# untitled.net
KiCad netlist of a schematic drawn in EAGLE
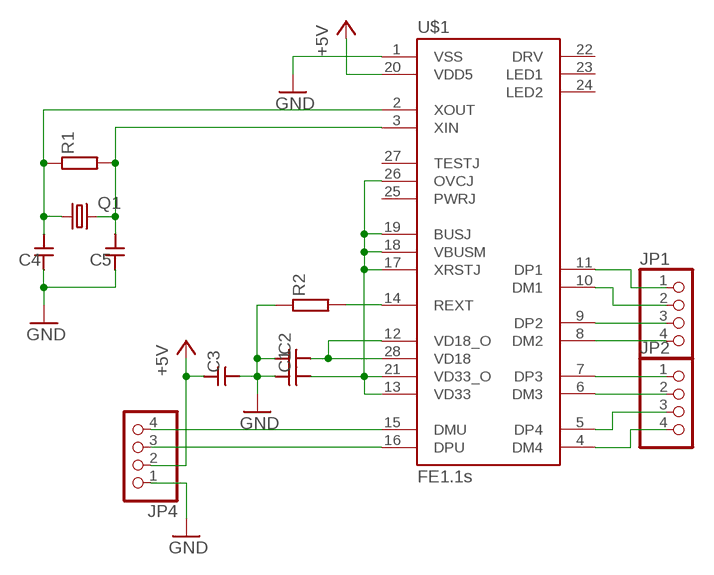
[diagram p0: schematic, sheet 1]

(export (version "E")
  (design (tool "Eeschema 10.0.6"))
  (components
    (comp (ref "C1")
      (value "CAPACITOR1608")
      (footprint "eagle-import:SMD1608")
      (libsource (lib "eagle-import") (part "CAPACITOR1608"))
    )
    (comp (ref "C2")
      (value "CAPACITOR1608")
      (footprint "eagle-import:SMD1608")
      (libsource (lib "eagle-import") (part "CAPACITOR1608"))
    )
    (comp (ref "C3")
      (value "CAPACITOR1608")
      (footprint "eagle-import:SMD1608")
      (libsource (lib "eagle-import") (part "CAPACITOR1608"))
    )
    (comp (ref "C4")
      (value "CAPACITOR1608")
      (footprint "eagle-import:SMD1608")
      (libsource (lib "eagle-import") (part "CAPACITOR1608"))
    )
    (comp (ref "C5")
      (value "CAPACITOR1608")
      (footprint "eagle-import:SMD1608")
      (libsource (lib "eagle-import") (part "CAPACITOR1608"))
    )
    (comp (ref "JP1")
      (value "PINHD-1X4")
      (footprint "eagle-import:1X04")
      (libsource (lib "eagle-import") (part "PINHD-1X4"))
    )
    (comp (ref "JP2")
      (value "PINHD-1X4")
      (footprint "eagle-import:1X04")
      (libsource (lib "eagle-import") (part "PINHD-1X4"))
    )
    (comp (ref "JP4")
      (value "PINHD-1X4")
      (footprint "eagle-import:1X04")
      (libsource (lib "eagle-import") (part "PINHD-1X4"))
    )
    (comp (ref "Q1")
      (value "CRYSTALHC49S")
      (footprint "eagle-import:HC49_S")
      (libsource (lib "eagle-import") (part "CRYSTALHC49S"))
    )
    (comp (ref "R1")
      (value "RESISTOR1608")
      (footprint "eagle-import:SMD1608")
      (libsource (lib "eagle-import") (part "RESISTOR1608"))
    )
    (comp (ref "R2")
      (value "RESISTOR1608")
      (footprint "eagle-import:SMD1608")
      (libsource (lib "eagle-import") (part "RESISTOR1608"))
    )
    (comp (ref "U$1")
      (value "FE1.1S")
      (footprint "eagle-import:FE1.1S_SSOP-28")
      (libsource (lib "eagle-import") (part "FE1.1S"))
    )
  )
  (nets
    (net (code "1") (name "+5V") (class "Default")
      (node (ref "C3") (pin "1") (pinfunction "1_1") (pintype "passive"))
      (node (ref "JP4") (pin "2") (pinfunction "2_2") (pintype "passive"))
      (node (ref "U$1") (pin "20") (pinfunction "VDD5_20") (pintype "bidirectional"))
    )
    (net (code "2") (name "GND") (class "Default")
      (node (ref "C1") (pin "1") (pinfunction "1_1") (pintype "passive"))
      (node (ref "C2") (pin "1") (pinfunction "1_1") (pintype "passive"))
      (node (ref "C3") (pin "2") (pinfunction "2_2") (pintype "passive"))
      (node (ref "C4") (pin "1") (pinfunction "1_1") (pintype "passive"))
      (node (ref "C5") (pin "1") (pinfunction "1_1") (pintype "passive"))
      (node (ref "JP4") (pin "1") (pinfunction "1_1") (pintype "passive"))
      (node (ref "R2") (pin "1") (pinfunction "1_1") (pintype "passive"))
      (node (ref "U$1") (pin "1") (pinfunction "VSS_1") (pintype "bidirectional"))
    )
    (net (code "3") (name "Net-(U$1-BUSJ)") (class "Default")
      (node (ref "C1") (pin "2") (pinfunction "2_2") (pintype "passive"))
      (node (ref "U$1") (pin "13") (pinfunction "VD33_13") (pintype "bidirectional"))
      (node (ref "U$1") (pin "17") (pinfunction "XRSTJ_17") (pintype "bidirectional"))
      (node (ref "U$1") (pin "18") (pinfunction "VBUSM_18") (pintype "bidirectional"))
      (node (ref "U$1") (pin "19") (pinfunction "BUSJ_19") (pintype "bidirectional"))
      (node (ref "U$1") (pin "21") (pinfunction "VD33_O_21") (pintype "bidirectional"))
      (node (ref "U$1") (pin "26") (pinfunction "OVCJ_26") (pintype "bidirectional"))
    )
    (net (code "4") (name "Net-(U$1-DM1)") (class "Default")
      (node (ref "JP1") (pin "2") (pinfunction "2_2") (pintype "passive"))
      (node (ref "U$1") (pin "10") (pinfunction "DM1_10") (pintype "bidirectional"))
    )
    (net (code "5") (name "Net-(U$1-DM2)") (class "Default")
      (node (ref "JP1") (pin "4") (pinfunction "4_4") (pintype "passive"))
      (node (ref "U$1") (pin "8") (pinfunction "DM2_8") (pintype "bidirectional"))
    )
    (net (code "6") (name "Net-(U$1-DM3)") (class "Default")
      (node (ref "JP2") (pin "2") (pinfunction "2_2") (pintype "passive"))
      (node (ref "U$1") (pin "6") (pinfunction "DM3_6") (pintype "bidirectional"))
    )
    (net (code "7") (name "Net-(U$1-DM4)") (class "Default")
      (node (ref "JP2") (pin "4") (pinfunction "4_4") (pintype "passive"))
      (node (ref "U$1") (pin "4") (pinfunction "DM4_4") (pintype "bidirectional"))
    )
    (net (code "8") (name "Net-(U$1-DMU)") (class "Default")
      (node (ref "JP4") (pin "4") (pinfunction "4_4") (pintype "passive"))
      (node (ref "U$1") (pin "15") (pinfunction "DMU_15") (pintype "bidirectional"))
    )
    (net (code "9") (name "Net-(U$1-DP1)") (class "Default")
      (node (ref "JP1") (pin "1") (pinfunction "1_1") (pintype "passive"))
      (node (ref "U$1") (pin "11") (pinfunction "DP1_11") (pintype "bidirectional"))
    )
    (net (code "10") (name "Net-(U$1-DP2)") (class "Default")
      (node (ref "JP1") (pin "3") (pinfunction "3_3") (pintype "passive"))
      (node (ref "U$1") (pin "9") (pinfunction "DP2_9") (pintype "bidirectional"))
    )
    (net (code "11") (name "Net-(U$1-DP3)") (class "Default")
      (node (ref "JP2") (pin "1") (pinfunction "1_1") (pintype "passive"))
      (node (ref "U$1") (pin "7") (pinfunction "DP3_7") (pintype "bidirectional"))
    )
    (net (code "12") (name "Net-(U$1-DP4)") (class "Default")
      (node (ref "JP2") (pin "3") (pinfunction "3_3") (pintype "passive"))
      (node (ref "U$1") (pin "5") (pinfunction "DP4_5") (pintype "bidirectional"))
    )
    (net (code "13") (name "Net-(U$1-DPU)") (class "Default")
      (node (ref "JP4") (pin "3") (pinfunction "3_3") (pintype "passive"))
      (node (ref "U$1") (pin "16") (pinfunction "DPU_16") (pintype "bidirectional"))
    )
    (net (code "14") (name "Net-(U$1-REXT)") (class "Default")
      (node (ref "R2") (pin "2") (pinfunction "2_2") (pintype "passive"))
      (node (ref "U$1") (pin "14") (pinfunction "REXT_14") (pintype "bidirectional"))
    )
    (net (code "15") (name "Net-(U$1-VD18)") (class "Default")
      (node (ref "C2") (pin "2") (pinfunction "2_2") (pintype "passive"))
      (node (ref "U$1") (pin "12") (pinfunction "VD18_O_12") (pintype "bidirectional"))
      (node (ref "U$1") (pin "28") (pinfunction "VD18_28") (pintype "bidirectional"))
    )
    (net (code "16") (name "Net-(U$1-XIN)") (class "Default")
      (node (ref "C5") (pin "2") (pinfunction "2_2") (pintype "passive"))
      (node (ref "Q1") (pin "2") (pinfunction "2_2") (pintype "passive"))
      (node (ref "R1") (pin "2") (pinfunction "2_2") (pintype "passive"))
      (node (ref "U$1") (pin "3") (pinfunction "XIN_3") (pintype "bidirectional"))
    )
    (net (code "17") (name "Net-(U$1-XOUT)") (class "Default")
      (node (ref "C4") (pin "2") (pinfunction "2_2") (pintype "passive"))
      (node (ref "Q1") (pin "1") (pinfunction "1_1") (pintype "passive"))
      (node (ref "R1") (pin "1") (pinfunction "1_1") (pintype "passive"))
      (node (ref "U$1") (pin "2") (pinfunction "XOUT_2") (pintype "bidirectional"))
    )
    (net (code "18") (name "unconnected-(U$1-DRV-Pad22)") (class "Default")
      (node (ref "U$1") (pin "22") (pinfunction "DRV_22") (pintype "bidirectional"))
    )
    (net (code "19") (name "unconnected-(U$1-LED1-Pad23)") (class "Default")
      (node (ref "U$1") (pin "23") (pinfunction "LED1_23") (pintype "bidirectional"))
    )
    (net (code "20") (name "unconnected-(U$1-LED2-Pad24)") (class "Default")
      (node (ref "U$1") (pin "24") (pinfunction "LED2_24") (pintype "bidirectional"))
    )
    (net (code "21") (name "unconnected-(U$1-PWRJ-Pad25)") (class "Default")
      (node (ref "U$1") (pin "25") (pinfunction "PWRJ_25") (pintype "bidirectional"))
    )
    (net (code "22") (name "unconnected-(U$1-TESTJ-Pad27)") (class "Default")
      (node (ref "U$1") (pin "27") (pinfunction "TESTJ_27") (pintype "bidirectional"))
    )
  )
)
